# Sheet1.net
KiCad netlist of a schematic drawn in Altium Designer
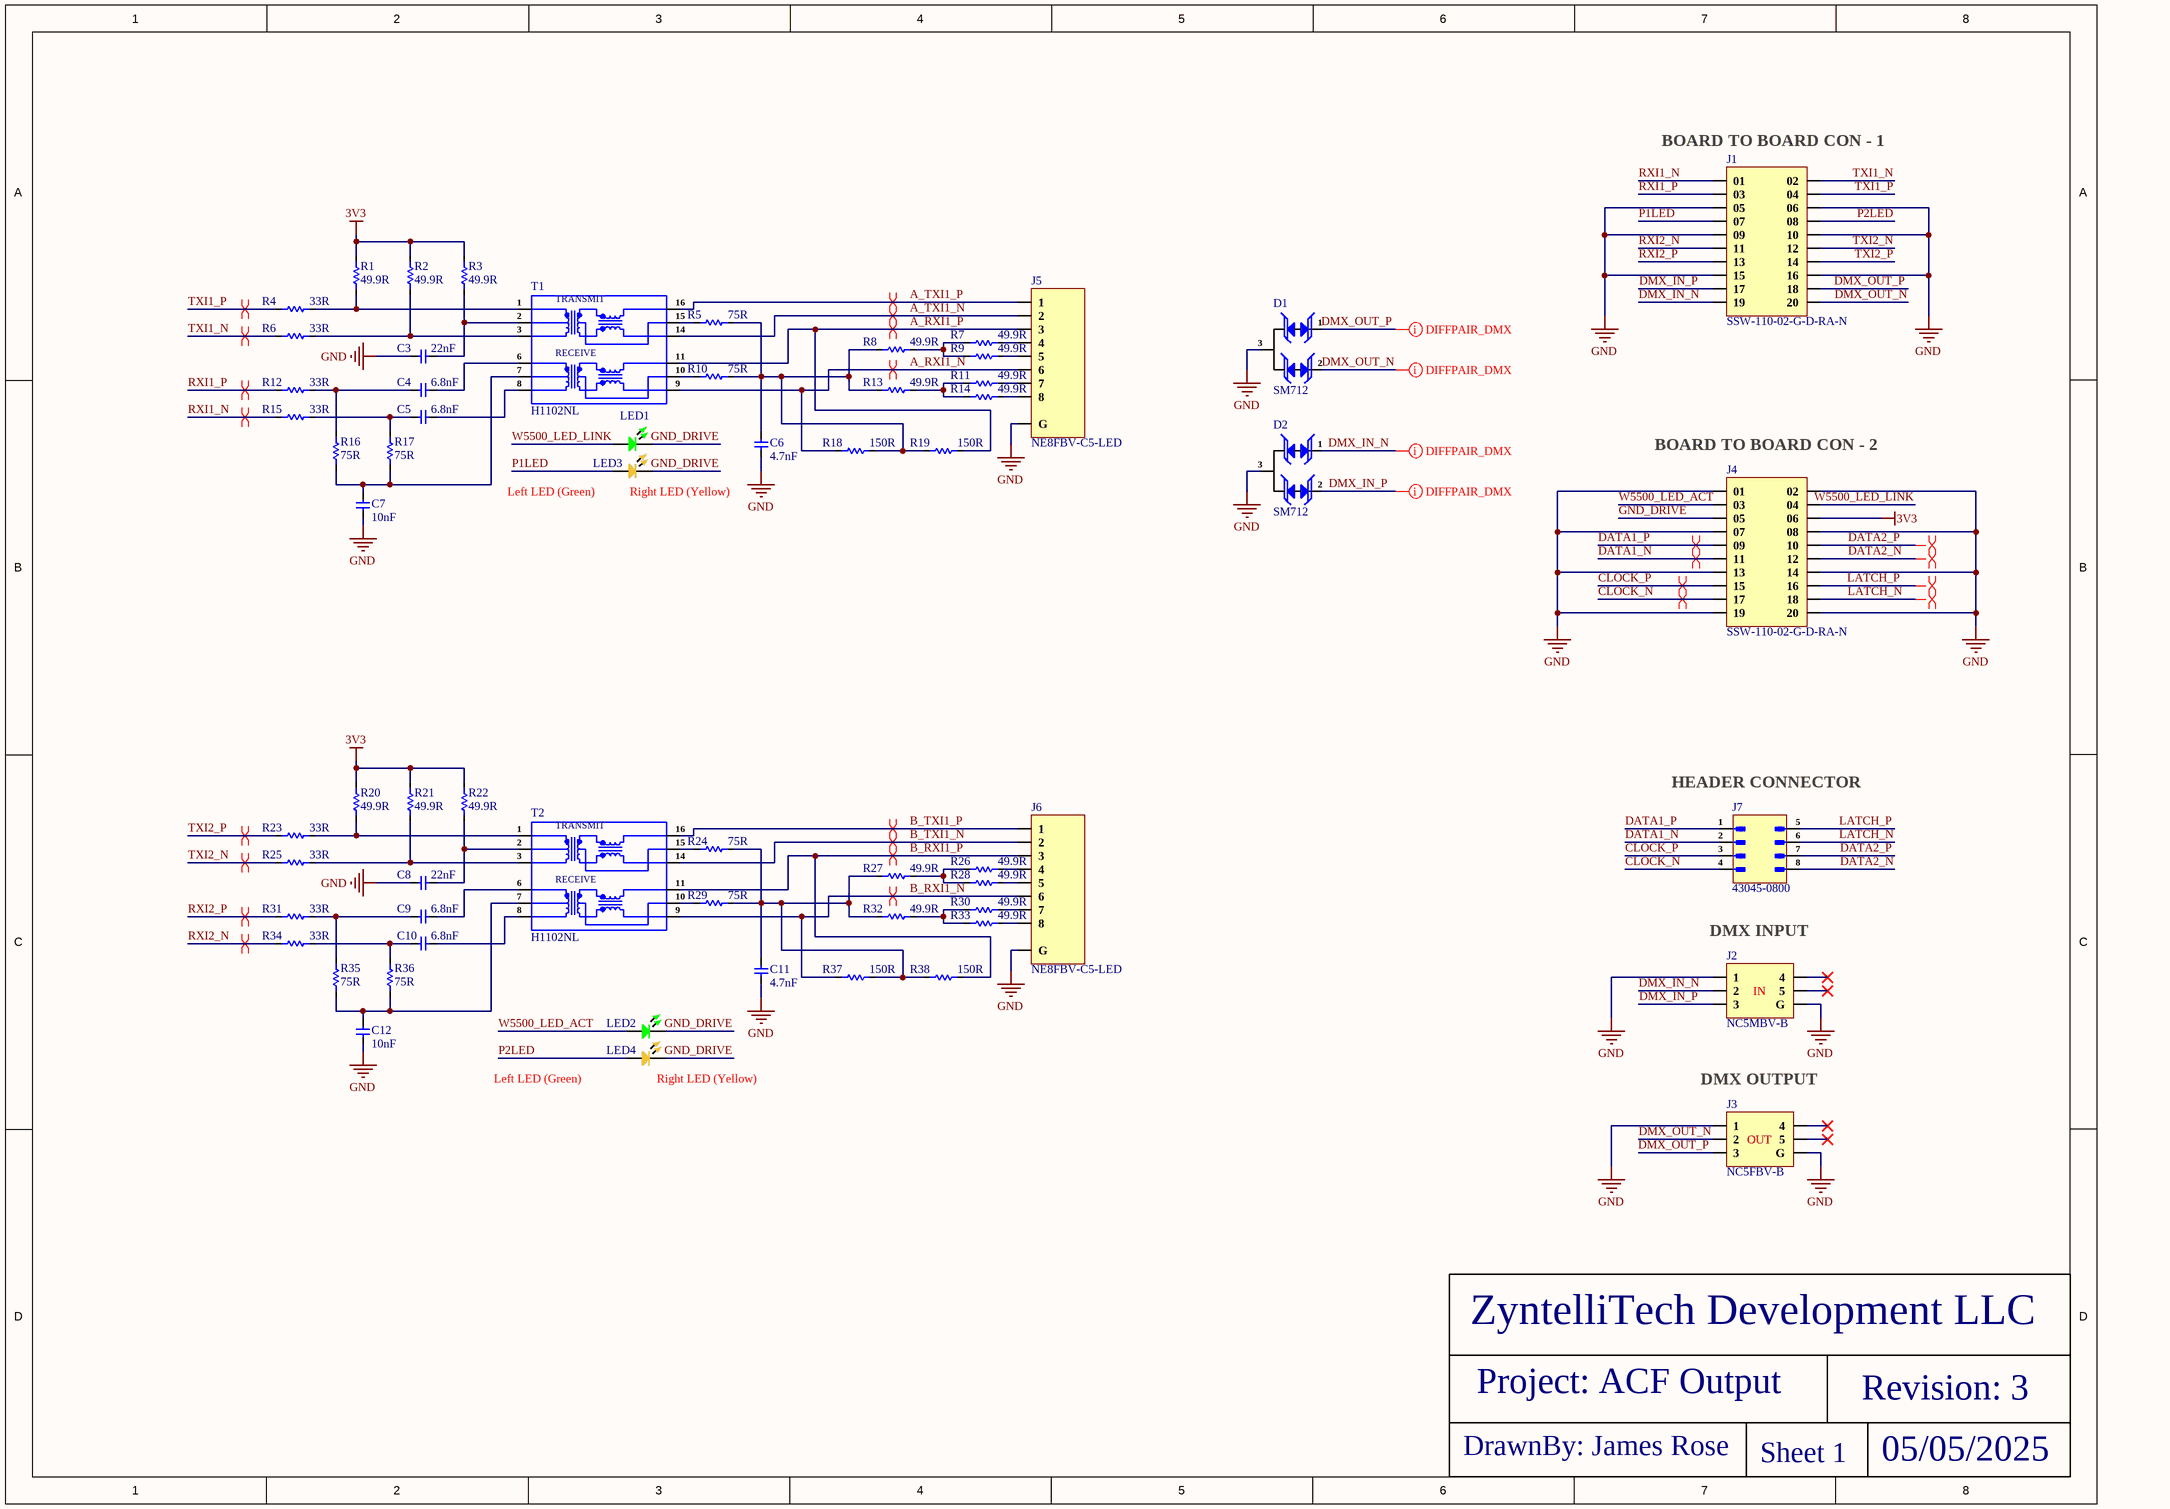
[diagram p0: Sheet1.SchDoc]

(export (version "E")
  (design (tool "Eeschema 10.0.6"))
  (components
    (comp (ref "C3")
      (value "22nF")
      (footprint "Cap-0603")
      (description "CAP CER 0.022UF 50V X7R 0603")
      (fields
        (field (name "MANUFACTURER") "Yageo")
        (field (name "MANUFACTURER PART NUMBER") "CC0603KRX7R9BB223")
      )
      (libsource (lib "eSpark Libraries") (part "CC0603KRX7R9BB223"))
    )
    (comp (ref "C4")
      (value "6.8nF")
      (footprint "Cap-0603")
      (description "50V 6.8nF X7R ±10% 0603")
      (fields (field (name "MANUFACTURER") "FH") (field (name "MANUFACTURER PART NUMBER") "0603B682K500NT"))
      (libsource (lib "eSpark Libraries") (part "0603B682K500NT"))
    )
    (comp (ref "C5")
      (value "6.8nF")
      (footprint "Cap-0603")
      (description "50V 6.8nF X7R ±10% 0603")
      (fields (field (name "MANUFACTURER") "FH") (field (name "MANUFACTURER PART NUMBER") "0603B682K500NT"))
      (libsource (lib "eSpark Libraries") (part "0603B682K500NT"))
    )
    (comp (ref "C6")
      (value "4.7nF")
      (footprint "Cap-1206")
      (description "CAP CER 4700PF 1KV X7R 1206")
      (fields
        (field (name "MANUFACTURER") "Yageo")
        (field (name "MANUFACTURER PART NUMBER") "CC1206KKX7RCBB472")
      )
      (libsource (lib "eSpark Libraries") (part "CC1206KKX7RCBB472"))
    )
    (comp (ref "C7")
      (value "10nF")
      (footprint "Cap-0603")
      (description "CAP CER 10000PF 100V X7R 0603")
      (fields (field (name "LCSC PART NUMBER") "C107059") (field (name "MANUFACTURER") "Yageo"))
      (libsource (lib "eSpark Libraries") (part "CC0603KRX7R0BB103"))
    )
    (comp (ref "C8")
      (value "22nF")
      (footprint "Cap-0603")
      (description "CAP CER 0.022UF 50V X7R 0603")
      (fields
        (field (name "MANUFACTURER") "Yageo")
        (field (name "MANUFACTURER PART NUMBER") "CC0603KRX7R9BB223")
      )
      (libsource (lib "eSpark Libraries") (part "CC0603KRX7R9BB223"))
    )
    (comp (ref "C9")
      (value "6.8nF")
      (footprint "Cap-0603")
      (description "50V 6.8nF X7R ±10% 0603")
      (fields (field (name "MANUFACTURER") "FH") (field (name "MANUFACTURER PART NUMBER") "0603B682K500NT"))
      (libsource (lib "eSpark Libraries") (part "0603B682K500NT"))
    )
    (comp (ref "C10")
      (value "6.8nF")
      (footprint "Cap-0603")
      (description "50V 6.8nF X7R ±10% 0603")
      (fields (field (name "MANUFACTURER") "FH") (field (name "MANUFACTURER PART NUMBER") "0603B682K500NT"))
      (libsource (lib "eSpark Libraries") (part "0603B682K500NT"))
    )
    (comp (ref "C11")
      (value "4.7nF")
      (footprint "Cap-1206")
      (description "CAP CER 4700PF 1KV X7R 1206")
      (fields
        (field (name "MANUFACTURER") "Yageo")
        (field (name "MANUFACTURER PART NUMBER") "CC1206KKX7RCBB472")
      )
      (libsource (lib "eSpark Libraries") (part "CC1206KKX7RCBB472"))
    )
    (comp (ref "C12")
      (value "10nF")
      (footprint "Cap-0603")
      (description "CAP CER 10000PF 100V X7R 0603")
      (fields (field (name "LCSC PART NUMBER") "C107059") (field (name "MANUFACTURER") "Yageo"))
      (libsource (lib "eSpark Libraries") (part "CC0603KRX7R0BB103"))
    )
    (comp (ref "D1")
      (value "SM712")
      (footprint "SOT-23")
      (description "SOT-23 TVS ROHS")
      (fields (field (name "MANUFACTURER") "TECH PUBLIC") (field (name "LCSC PART NUMBER") "C521963"))
      (libsource (lib "eSpark Libraries") (part "SM712"))
    )
    (comp (ref "D2")
      (value "SM712")
      (footprint "SOT-23")
      (description "SOT-23 TVS ROHS")
      (fields (field (name "MANUFACTURER") "TECH PUBLIC") (field (name "LCSC PART NUMBER") "C521963"))
      (libsource (lib "eSpark Libraries") (part "SM712"))
    )
    (comp (ref "J1")
      (value "SSW-110-02-G-D-RA-N")
      (footprint "SSW-110-02-G-D-RA-N")
      (description "CONN RCPT 20POS 0.1 GOLD PCB R/A")
      (fields (field (name "MANUFACTURER") "Samtec"))
      (libsource (lib "eSpark Libraries") (part "SSW-110-02-G-D-RA-N"))
    )
    (comp (ref "J2")
      (value "NC5MBV-B")
      (footprint "NC5MBV-B")
      (description "XLR Connectors 5P M RECEPT B SER PCBV PN 1 GRD SEP BK")
      (fields (field (name "MANUFACTURER") "Neutrik"))
      (libsource (lib "eSpark Libraries") (part "NC5MBV-B"))
    )
    (comp (ref "J3")
      (value "NC5FBV-B")
      (footprint "NC5FBV-B")
      (description "XLR Connectors 5P M RECEPT B SER PCBV PN 1 GRD SEP BK")
      (fields (field (name "MANUFACTURER") "Neutrik"))
      (libsource (lib "eSpark Libraries") (part "NC5FBV-B"))
    )
    (comp (ref "J4")
      (value "SSW-110-02-G-D-RA-N")
      (footprint "SSW-110-02-G-D-RA-N")
      (description "CONN RCPT 20POS 0.1 GOLD PCB R/A")
      (fields (field (name "MANUFACTURER") "Samtec"))
      (libsource (lib "eSpark Libraries") (part "SSW-110-02-G-D-RA-N"))
    )
    (comp (ref "J5")
      (value "NE8FBV-C5-LED")
      (footprint "NE8FBV-C5-LED")
      (description "Modular Connectors / Ethernet Connectors RECP CAT5e B series PCBV, 24mm FP to PCB")
      (fields (field (name "MANUFACTURER") "Neutrik"))
      (libsource (lib "eSpark Libraries") (part "NE8FBV-C5-LED"))
    )
    (comp (ref "J6")
      (value "NE8FBV-C5-LED")
      (footprint "NE8FBV-C5-LED")
      (description "Modular Connectors / Ethernet Connectors RECP CAT5e B series PCBV, 24mm FP to PCB")
      (fields (field (name "MANUFACTURER") "Neutrik"))
      (libsource (lib "eSpark Libraries") (part "NE8FBV-C5-LED"))
    )
    (comp (ref "J7")
      (value "43045-0800")
      (footprint "0430450800")
      (description "CONN HEADER R/A 8POS 3MM")
      (fields (field (name "MANUFACTURER") "Molex"))
      (libsource (lib "eSpark Libraries") (part "43045-0800"))
    )
    (comp (ref "LED1")
      (value "Emerald")
      (footprint "TH LED 3mm_")
      (description "515nm~525nm -30℃~+85℃ Emerald 30° 200mW Plugin,D=3mm Light Emitting Diodes (LED) ROHS")
      (fields
        (field (name "MANUFACTURER") "Foshan NationStar Optoelectronics")
        (field (name "MANUFACTURER PART NUMBER") "NFD3401UGD")
      )
      (libsource (lib "eSpark Libraries") (part "NFD3401UGD"))
    )
    (comp (ref "LED2")
      (value "Emerald")
      (footprint "TH LED 3mm_")
      (description "515nm~525nm -30℃~+85℃ Emerald 30° 200mW Plugin,D=3mm Light Emitting Diodes (LED) ROHS")
      (fields
        (field (name "MANUFACTURER") "Foshan NationStar Optoelectronics")
        (field (name "MANUFACTURER PART NUMBER") "NFD3401UGD")
      )
      (libsource (lib "eSpark Libraries") (part "NFD3401UGD"))
    )
    (comp (ref "LED3")
      (value "Yellow")
      (footprint "TH LED Yellow 3MM")
      (description "585nm~595nm -30℃~+85℃ Yellow 30° 200mW Plugin,D=3mm Light Emitting Diodes (LED) ROHS")
      (fields
        (field (name "MANUFACTURER") "Foshan NationStar Optoelectronics")
        (field (name "MANUFACTURER PART NUMBER") "NFD3401UYD")
      )
      (libsource (lib "eSpark Libraries") (part "NFD3401UYD"))
    )
    (comp (ref "LED4")
      (value "Yellow")
      (footprint "TH LED Yellow 3MM")
      (description "585nm~595nm -30℃~+85℃ Yellow 30° 200mW Plugin,D=3mm Light Emitting Diodes (LED) ROHS")
      (fields
        (field (name "MANUFACTURER") "Foshan NationStar Optoelectronics")
        (field (name "MANUFACTURER PART NUMBER") "NFD3401UYD")
      )
      (libsource (lib "eSpark Libraries") (part "NFD3401UYD"))
    )
    (comp (ref "R1")
      (value "49.9R")
      (footprint "Res-0603")
      (description "RES 49.9 OHM 1% 1/10W 0603")
      (fields
        (field (name "MANUFACTURER") "Yageo")
        (field (name "MANUFACTURER PART NUMBER") "RC0603FR-0749R9L")
      )
      (libsource (lib "eSpark Libraries") (part "RC0603FR-0749R9L"))
    )
    (comp (ref "R2")
      (value "49.9R")
      (footprint "Res-0603")
      (description "RES 49.9 OHM 1% 1/10W 0603")
      (fields
        (field (name "MANUFACTURER") "Yageo")
        (field (name "MANUFACTURER PART NUMBER") "RC0603FR-0749R9L")
      )
      (libsource (lib "eSpark Libraries") (part "RC0603FR-0749R9L"))
    )
    (comp (ref "R3")
      (value "49.9R")
      (footprint "Res-0603")
      (description "RES 49.9 OHM 1% 1/10W 0603")
      (fields
        (field (name "MANUFACTURER") "Yageo")
        (field (name "MANUFACTURER PART NUMBER") "RC0603FR-0749R9L")
      )
      (libsource (lib "eSpark Libraries") (part "RC0603FR-0749R9L"))
    )
    (comp (ref "R4")
      (value "33R")
      (footprint "Res-0603")
      (description "RES SMD 0603 33 Ohm 1% 1/10W")
      (fields
        (field (name "MANUFACTURER") "Yageo")
        (field (name "MANUFACTURER PART NUMBER") "RC0603FR-0733RL")
      )
      (libsource (lib "eSpark Libraries") (part "RC0603FR-0733RL"))
    )
    (comp (ref "R5")
      (value "75R")
      (footprint "Res-0603")
      (description "RES 75 OHM 1% 1/10W 0603")
      (fields
        (field (name "MANUFACTURER") "Yageo")
        (field (name "MANUFACTURER PART NUMBER") "RC0603FR-0775RL")
      )
      (libsource (lib "eSpark Libraries") (part "RC0603FR-0775RL"))
    )
    (comp (ref "R6")
      (value "33R")
      (footprint "Res-0603")
      (description "RES SMD 0603 33 Ohm 1% 1/10W")
      (fields
        (field (name "MANUFACTURER") "Yageo")
        (field (name "MANUFACTURER PART NUMBER") "RC0603FR-0733RL")
      )
      (libsource (lib "eSpark Libraries") (part "RC0603FR-0733RL"))
    )
    (comp (ref "R7")
      (value "49.9R")
      (footprint "Res-0603")
      (description "RES 49.9 OHM 1% 1/10W 0603")
      (fields
        (field (name "MANUFACTURER") "Yageo")
        (field (name "MANUFACTURER PART NUMBER") "RC0603FR-0749R9L")
      )
      (libsource (lib "eSpark Libraries") (part "RC0603FR-0749R9L"))
    )
    (comp (ref "R8")
      (value "49.9R")
      (footprint "Res-0603")
      (description "RES 49.9 OHM 1% 1/10W 0603")
      (fields
        (field (name "MANUFACTURER") "Yageo")
        (field (name "MANUFACTURER PART NUMBER") "RC0603FR-0749R9L")
      )
      (libsource (lib "eSpark Libraries") (part "RC0603FR-0749R9L"))
    )
    (comp (ref "R9")
      (value "49.9R")
      (footprint "Res-0603")
      (description "RES 49.9 OHM 1% 1/10W 0603")
      (fields
        (field (name "MANUFACTURER") "Yageo")
        (field (name "MANUFACTURER PART NUMBER") "RC0603FR-0749R9L")
      )
      (libsource (lib "eSpark Libraries") (part "RC0603FR-0749R9L"))
    )
    (comp (ref "R10")
      (value "75R")
      (footprint "Res-0603")
      (description "RES 75 OHM 1% 1/10W 0603")
      (fields
        (field (name "MANUFACTURER") "Yageo")
        (field (name "MANUFACTURER PART NUMBER") "RC0603FR-0775RL")
      )
      (libsource (lib "eSpark Libraries") (part "RC0603FR-0775RL"))
    )
    (comp (ref "R11")
      (value "49.9R")
      (footprint "Res-0603")
      (description "RES 49.9 OHM 1% 1/10W 0603")
      (fields
        (field (name "MANUFACTURER") "Yageo")
        (field (name "MANUFACTURER PART NUMBER") "RC0603FR-0749R9L")
      )
      (libsource (lib "eSpark Libraries") (part "RC0603FR-0749R9L"))
    )
    (comp (ref "R12")
      (value "33R")
      (footprint "Res-0603")
      (description "RES SMD 0603 33 Ohm 1% 1/10W")
      (fields
        (field (name "MANUFACTURER") "Yageo")
        (field (name "MANUFACTURER PART NUMBER") "RC0603FR-0733RL")
      )
      (libsource (lib "eSpark Libraries") (part "RC0603FR-0733RL"))
    )
    (comp (ref "R13")
      (value "49.9R")
      (footprint "Res-0603")
      (description "RES 49.9 OHM 1% 1/10W 0603")
      (fields
        (field (name "MANUFACTURER") "Yageo")
        (field (name "MANUFACTURER PART NUMBER") "RC0603FR-0749R9L")
      )
      (libsource (lib "eSpark Libraries") (part "RC0603FR-0749R9L"))
    )
    (comp (ref "R14")
      (value "49.9R")
      (footprint "Res-0603")
      (description "RES 49.9 OHM 1% 1/10W 0603")
      (fields
        (field (name "MANUFACTURER") "Yageo")
        (field (name "MANUFACTURER PART NUMBER") "RC0603FR-0749R9L")
      )
      (libsource (lib "eSpark Libraries") (part "RC0603FR-0749R9L"))
    )
    (comp (ref "R15")
      (value "33R")
      (footprint "Res-0603")
      (description "RES SMD 0603 33 Ohm 1% 1/10W")
      (fields
        (field (name "MANUFACTURER") "Yageo")
        (field (name "MANUFACTURER PART NUMBER") "RC0603FR-0733RL")
      )
      (libsource (lib "eSpark Libraries") (part "RC0603FR-0733RL"))
    )
    (comp (ref "R16")
      (value "75R")
      (footprint "Res-0603")
      (description "RES 75 OHM 1% 1/10W 0603")
      (fields
        (field (name "MANUFACTURER") "Yageo")
        (field (name "MANUFACTURER PART NUMBER") "RC0603FR-0775RL")
      )
      (libsource (lib "eSpark Libraries") (part "RC0603FR-0775RL"))
    )
    (comp (ref "R17")
      (value "75R")
      (footprint "Res-0603")
      (description "RES 75 OHM 1% 1/10W 0603")
      (fields
        (field (name "MANUFACTURER") "Yageo")
        (field (name "MANUFACTURER PART NUMBER") "RC0603FR-0775RL")
      )
      (libsource (lib "eSpark Libraries") (part "RC0603FR-0775RL"))
    )
    (comp (ref "R18")
      (value "150R")
      (footprint "Res-0603")
      (description "RES SMD 150OHM 1/10W 0603")
      (fields
        (field (name "MANUFACTURER") "Yageo")
        (field (name "MANUFACTURER PART NUMBER") "RC0603FR-07150RL")
      )
      (libsource (lib "eSpark Libraries") (part "RC0603FR-07150RL"))
    )
    (comp (ref "R19")
      (value "150R")
      (footprint "Res-0603")
      (description "RES SMD 150OHM 1/10W 0603")
      (fields
        (field (name "MANUFACTURER") "Yageo")
        (field (name "MANUFACTURER PART NUMBER") "RC0603FR-07150RL")
      )
      (libsource (lib "eSpark Libraries") (part "RC0603FR-07150RL"))
    )
    (comp (ref "R20")
      (value "49.9R")
      (footprint "Res-0603")
      (description "RES 49.9 OHM 1% 1/10W 0603")
      (fields
        (field (name "MANUFACTURER") "Yageo")
        (field (name "MANUFACTURER PART NUMBER") "RC0603FR-0749R9L")
      )
      (libsource (lib "eSpark Libraries") (part "RC0603FR-0749R9L"))
    )
    (comp (ref "R21")
      (value "49.9R")
      (footprint "Res-0603")
      (description "RES 49.9 OHM 1% 1/10W 0603")
      (fields
        (field (name "MANUFACTURER") "Yageo")
        (field (name "MANUFACTURER PART NUMBER") "RC0603FR-0749R9L")
      )
      (libsource (lib "eSpark Libraries") (part "RC0603FR-0749R9L"))
    )
    (comp (ref "R22")
      (value "49.9R")
      (footprint "Res-0603")
      (description "RES 49.9 OHM 1% 1/10W 0603")
      (fields
        (field (name "MANUFACTURER") "Yageo")
        (field (name "MANUFACTURER PART NUMBER") "RC0603FR-0749R9L")
      )
      (libsource (lib "eSpark Libraries") (part "RC0603FR-0749R9L"))
    )
    (comp (ref "R23")
      (value "33R")
      (footprint "Res-0603")
      (description "RES SMD 0603 33 Ohm 1% 1/10W")
      (fields
        (field (name "MANUFACTURER") "Yageo")
        (field (name "MANUFACTURER PART NUMBER") "RC0603FR-0733RL")
      )
      (libsource (lib "eSpark Libraries") (part "RC0603FR-0733RL"))
    )
    (comp (ref "R24")
      (value "75R")
      (footprint "Res-0603")
      (description "RES 75 OHM 1% 1/10W 0603")
      (fields
        (field (name "MANUFACTURER") "Yageo")
        (field (name "MANUFACTURER PART NUMBER") "RC0603FR-0775RL")
      )
      (libsource (lib "eSpark Libraries") (part "RC0603FR-0775RL"))
    )
    (comp (ref "R25")
      (value "33R")
      (footprint "Res-0603")
      (description "RES SMD 0603 33 Ohm 1% 1/10W")
      (fields
        (field (name "MANUFACTURER") "Yageo")
        (field (name "MANUFACTURER PART NUMBER") "RC0603FR-0733RL")
      )
      (libsource (lib "eSpark Libraries") (part "RC0603FR-0733RL"))
    )
    (comp (ref "R26")
      (value "49.9R")
      (footprint "Res-0603")
      (description "RES 49.9 OHM 1% 1/10W 0603")
      (fields
        (field (name "MANUFACTURER") "Yageo")
        (field (name "MANUFACTURER PART NUMBER") "RC0603FR-0749R9L")
      )
      (libsource (lib "eSpark Libraries") (part "RC0603FR-0749R9L"))
    )
    (comp (ref "R27")
      (value "49.9R")
      (footprint "Res-0603")
      (description "RES 49.9 OHM 1% 1/10W 0603")
      (fields
        (field (name "MANUFACTURER") "Yageo")
        (field (name "MANUFACTURER PART NUMBER") "RC0603FR-0749R9L")
      )
      (libsource (lib "eSpark Libraries") (part "RC0603FR-0749R9L"))
    )
    (comp (ref "R28")
      (value "49.9R")
      (footprint "Res-0603")
      (description "RES 49.9 OHM 1% 1/10W 0603")
      (fields
        (field (name "MANUFACTURER") "Yageo")
        (field (name "MANUFACTURER PART NUMBER") "RC0603FR-0749R9L")
      )
      (libsource (lib "eSpark Libraries") (part "RC0603FR-0749R9L"))
    )
    (comp (ref "R29")
      (value "75R")
      (footprint "Res-0603")
      (description "RES 75 OHM 1% 1/10W 0603")
      (fields
        (field (name "MANUFACTURER") "Yageo")
        (field (name "MANUFACTURER PART NUMBER") "RC0603FR-0775RL")
      )
      (libsource (lib "eSpark Libraries") (part "RC0603FR-0775RL"))
    )
    (comp (ref "R30")
      (value "49.9R")
      (footprint "Res-0603")
      (description "RES 49.9 OHM 1% 1/10W 0603")
      (fields
        (field (name "MANUFACTURER") "Yageo")
        (field (name "MANUFACTURER PART NUMBER") "RC0603FR-0749R9L")
      )
      (libsource (lib "eSpark Libraries") (part "RC0603FR-0749R9L"))
    )
    (comp (ref "R31")
      (value "33R")
      (footprint "Res-0603")
      (description "RES SMD 0603 33 Ohm 1% 1/10W")
      (fields
        (field (name "MANUFACTURER") "Yageo")
        (field (name "MANUFACTURER PART NUMBER") "RC0603FR-0733RL")
      )
      (libsource (lib "eSpark Libraries") (part "RC0603FR-0733RL"))
    )
    (comp (ref "R32")
      (value "49.9R")
      (footprint "Res-0603")
      (description "RES 49.9 OHM 1% 1/10W 0603")
      (fields
        (field (name "MANUFACTURER") "Yageo")
        (field (name "MANUFACTURER PART NUMBER") "RC0603FR-0749R9L")
      )
      (libsource (lib "eSpark Libraries") (part "RC0603FR-0749R9L"))
    )
    (comp (ref "R33")
      (value "49.9R")
      (footprint "Res-0603")
      (description "RES 49.9 OHM 1% 1/10W 0603")
      (fields
        (field (name "MANUFACTURER") "Yageo")
        (field (name "MANUFACTURER PART NUMBER") "RC0603FR-0749R9L")
      )
      (libsource (lib "eSpark Libraries") (part "RC0603FR-0749R9L"))
    )
    (comp (ref "R34")
      (value "33R")
      (footprint "Res-0603")
      (description "RES SMD 0603 33 Ohm 1% 1/10W")
      (fields
        (field (name "MANUFACTURER") "Yageo")
        (field (name "MANUFACTURER PART NUMBER") "RC0603FR-0733RL")
      )
      (libsource (lib "eSpark Libraries") (part "RC0603FR-0733RL"))
    )
    (comp (ref "R35")
      (value "75R")
      (footprint "Res-0603")
      (description "RES 75 OHM 1% 1/10W 0603")
      (fields
        (field (name "MANUFACTURER") "Yageo")
        (field (name "MANUFACTURER PART NUMBER") "RC0603FR-0775RL")
      )
      (libsource (lib "eSpark Libraries") (part "RC0603FR-0775RL"))
    )
    (comp (ref "R36")
      (value "75R")
      (footprint "Res-0603")
      (description "RES 75 OHM 1% 1/10W 0603")
      (fields
        (field (name "MANUFACTURER") "Yageo")
        (field (name "MANUFACTURER PART NUMBER") "RC0603FR-0775RL")
      )
      (libsource (lib "eSpark Libraries") (part "RC0603FR-0775RL"))
    )
    (comp (ref "R37")
      (value "150R")
      (footprint "Res-0603")
      (description "RES SMD 150OHM 1/10W 0603")
      (fields
        (field (name "MANUFACTURER") "Yageo")
        (field (name "MANUFACTURER PART NUMBER") "RC0603FR-07150RL")
      )
      (libsource (lib "eSpark Libraries") (part "RC0603FR-07150RL"))
    )
    (comp (ref "R38")
      (value "150R")
      (footprint "Res-0603")
      (description "RES SMD 150OHM 1/10W 0603")
      (fields
        (field (name "MANUFACTURER") "Yageo")
        (field (name "MANUFACTURER PART NUMBER") "RC0603FR-07150RL")
      )
      (libsource (lib "eSpark Libraries") (part "RC0603FR-07150RL"))
    )
    (comp (ref "T1")
      (value "H1102NL")
      (footprint "H1102NLT")
      (description "XFRMR MAGNETIC 1PORT 1:1 10/100")
      (fields (field (name "MANUFACTURER") "Pulse") (field (name "LCSC PART NUMBER") "C18584"))
      (libsource (lib "eSpark Libraries") (part "H1102NL"))
    )
    (comp (ref "T2")
      (value "H1102NL")
      (footprint "H1102NLT")
      (description "XFRMR MAGNETIC 1PORT 1:1 10/100")
      (fields (field (name "MANUFACTURER") "Pulse") (field (name "LCSC PART NUMBER") "C18584"))
      (libsource (lib "eSpark Libraries") (part "H1102NL"))
    )
  )
  (nets
    (net (code "1") (name "/A_RXI1_N") (class "Default")
      (node (ref "J5") (pin "6") (pinfunction "6_6") (pintype "passive"))
      (node (ref "R18") (pin "2") (pinfunction "2_2") (pintype "passive"))
      (node (ref "T1") (pin "9") (pinfunction "9_9") (pintype "passive"))
    )
    (net (code "2") (name "/A_RXI1_P") (class "Default")
      (node (ref "J5") (pin "3") (pinfunction "3_3") (pintype "passive"))
      (node (ref "R19") (pin "1") (pinfunction "1_1") (pintype "passive"))
      (node (ref "T1") (pin "11") (pinfunction "11_11") (pintype "passive"))
    )
    (net (code "3") (name "/A_TXI1_N") (class "Default")
      (node (ref "J5") (pin "2") (pinfunction "2_2") (pintype "passive"))
      (node (ref "T1") (pin "14") (pinfunction "14_14") (pintype "passive"))
    )
    (net (code "4") (name "/A_TXI1_P") (class "Default")
      (node (ref "J5") (pin "1") (pinfunction "1_1") (pintype "passive"))
      (node (ref "T1") (pin "16") (pinfunction "16_16") (pintype "passive"))
    )
    (net (code "5") (name "/B_RXI1_N") (class "Default")
      (node (ref "J6") (pin "6") (pinfunction "6_6") (pintype "passive"))
      (node (ref "R37") (pin "2") (pinfunction "2_2") (pintype "passive"))
      (node (ref "T2") (pin "9") (pinfunction "9_9") (pintype "passive"))
    )
    (net (code "6") (name "/B_RXI1_P") (class "Default")
      (node (ref "J6") (pin "3") (pinfunction "3_3") (pintype "passive"))
      (node (ref "R38") (pin "1") (pinfunction "1_1") (pintype "passive"))
      (node (ref "T2") (pin "11") (pinfunction "11_11") (pintype "passive"))
    )
    (net (code "7") (name "/B_TXI1_N") (class "Default")
      (node (ref "J6") (pin "2") (pinfunction "2_2") (pintype "passive"))
      (node (ref "T2") (pin "14") (pinfunction "14_14") (pintype "passive"))
    )
    (net (code "8") (name "/B_TXI1_P") (class "Default")
      (node (ref "J6") (pin "1") (pinfunction "1_1") (pintype "passive"))
      (node (ref "T2") (pin "16") (pinfunction "16_16") (pintype "passive"))
    )
    (net (code "9") (name "/CLOCK_N") (class "Default")
      (node (ref "J4") (pin "17") (pinfunction "17_17") (pintype "passive"))
      (node (ref "J7") (pin "4") (pinfunction "4_4") (pintype "passive"))
    )
    (net (code "10") (name "/CLOCK_P") (class "Default")
      (node (ref "J4") (pin "15") (pinfunction "15_15") (pintype "passive"))
      (node (ref "J7") (pin "3") (pinfunction "3_3") (pintype "passive"))
    )
    (net (code "11") (name "/DATA1_N") (class "Default")
      (node (ref "J4") (pin "11") (pinfunction "11_11") (pintype "passive"))
      (node (ref "J7") (pin "2") (pinfunction "2_2") (pintype "passive"))
    )
    (net (code "12") (name "/DATA1_P") (class "Default")
      (node (ref "J4") (pin "09") (pinfunction "09_09") (pintype "passive"))
      (node (ref "J7") (pin "1") (pinfunction "1_1") (pintype "passive"))
    )
    (net (code "13") (name "/DATA2_N") (class "Default")
      (node (ref "J4") (pin "12") (pinfunction "12_12") (pintype "passive"))
      (node (ref "J7") (pin "8") (pinfunction "8_8") (pintype "passive"))
    )
    (net (code "14") (name "/DATA2_P") (class "Default")
      (node (ref "J4") (pin "10") (pinfunction "10_10") (pintype "passive"))
      (node (ref "J7") (pin "7") (pinfunction "7_7") (pintype "passive"))
    )
    (net (code "15") (name "/DMX_IN_N") (class "Default")
      (node (ref "D2") (pin "1") (pinfunction "I/O1_1") (pintype "passive"))
      (node (ref "J1") (pin "19") (pinfunction "19_19") (pintype "passive"))
      (node (ref "J2") (pin "2") (pinfunction "2_2") (pintype "passive"))
    )
    (net (code "16") (name "/DMX_IN_P") (class "Default")
      (node (ref "D2") (pin "2") (pinfunction "I/O2_2") (pintype "passive"))
      (node (ref "J1") (pin "17") (pinfunction "17_17") (pintype "passive"))
      (node (ref "J2") (pin "3") (pinfunction "3_3") (pintype "passive"))
    )
    (net (code "17") (name "/DMX_OUT_N") (class "Default")
      (node (ref "D1") (pin "2") (pinfunction "I/O2_2") (pintype "passive"))
      (node (ref "J1") (pin "20") (pinfunction "20_20") (pintype "passive"))
      (node (ref "J3") (pin "2") (pinfunction "2_2") (pintype "passive"))
    )
    (net (code "18") (name "/DMX_OUT_P") (class "Default")
      (node (ref "D1") (pin "1") (pinfunction "I/O1_1") (pintype "passive"))
      (node (ref "J1") (pin "18") (pinfunction "18_18") (pintype "passive"))
      (node (ref "J3") (pin "3") (pinfunction "3_3") (pintype "passive"))
    )
    (net (code "19") (name "/GND_DRIVE") (class "Default")
      (node (ref "J4") (pin "05") (pinfunction "05_05") (pintype "passive"))
      (node (ref "LED1") (pin "1") (pinfunction "-_1") (pintype "passive"))
      (node (ref "LED2") (pin "1") (pinfunction "-_1") (pintype "passive"))
      (node (ref "LED3") (pin "2") (pinfunction "2_2") (pintype "passive"))
      (node (ref "LED4") (pin "2") (pinfunction "2_2") (pintype "passive"))
    )
    (net (code "20") (name "/LATCH_N") (class "Default")
      (node (ref "J4") (pin "18") (pinfunction "18_18") (pintype "passive"))
      (node (ref "J7") (pin "6") (pinfunction "6_6") (pintype "passive"))
    )
    (net (code "21") (name "/LATCH_P") (class "Default")
      (node (ref "J4") (pin "16") (pinfunction "16_16") (pintype "passive"))
      (node (ref "J7") (pin "5") (pinfunction "5_5") (pintype "passive"))
    )
    (net (code "22") (name "/P1LED") (class "Default")
      (node (ref "J1") (pin "07") (pinfunction "07_07") (pintype "passive"))
      (node (ref "LED3") (pin "1") (pinfunction "1_1") (pintype "passive"))
    )
    (net (code "23") (name "/P2LED") (class "Default")
      (node (ref "J1") (pin "08") (pinfunction "08_08") (pintype "passive"))
      (node (ref "LED4") (pin "1") (pinfunction "1_1") (pintype "passive"))
    )
    (net (code "24") (name "/RXI1_N") (class "Default")
      (node (ref "J1") (pin "01") (pinfunction "01_01") (pintype "passive"))
      (node (ref "R15") (pin "1") (pinfunction "1_1") (pintype "passive"))
    )
    (net (code "25") (name "/RXI1_P") (class "Default")
      (node (ref "J1") (pin "03") (pinfunction "03_03") (pintype "passive"))
      (node (ref "R12") (pin "1") (pinfunction "1_1") (pintype "passive"))
    )
    (net (code "26") (name "/RXI2_N") (class "Default")
      (node (ref "J1") (pin "11") (pinfunction "11_11") (pintype "passive"))
      (node (ref "R34") (pin "1") (pinfunction "1_1") (pintype "passive"))
    )
    (net (code "27") (name "/RXI2_P") (class "Default")
      (node (ref "J1") (pin "13") (pinfunction "13_13") (pintype "passive"))
      (node (ref "R31") (pin "1") (pinfunction "1_1") (pintype "passive"))
    )
    (net (code "28") (name "/TXI1_N") (class "Default")
      (node (ref "J1") (pin "02") (pinfunction "02_02") (pintype "passive"))
      (node (ref "R6") (pin "1") (pinfunction "1_1") (pintype "passive"))
    )
    (net (code "29") (name "/TXI1_P") (class "Default")
      (node (ref "J1") (pin "04") (pinfunction "04_04") (pintype "passive"))
      (node (ref "R4") (pin "1") (pinfunction "1_1") (pintype "passive"))
    )
    (net (code "30") (name "/TXI2_N") (class "Default")
      (node (ref "J1") (pin "12") (pinfunction "12_12") (pintype "passive"))
      (node (ref "R25") (pin "1") (pinfunction "1_1") (pintype "passive"))
    )
    (net (code "31") (name "/TXI2_P") (class "Default")
      (node (ref "J1") (pin "14") (pinfunction "14_14") (pintype "passive"))
      (node (ref "R23") (pin "1") (pinfunction "1_1") (pintype "passive"))
    )
    (net (code "32") (name "/W5500_LED_ACT") (class "Default")
      (node (ref "J4") (pin "03") (pinfunction "03_03") (pintype "passive"))
      (node (ref "LED2") (pin "2") (pinfunction "+_2") (pintype "passive"))
    )
    (net (code "33") (name "/W5500_LED_LINK") (class "Default")
      (node (ref "J4") (pin "04") (pinfunction "04_04") (pintype "passive"))
      (node (ref "LED1") (pin "2") (pinfunction "+_2") (pintype "passive"))
    )
    (net (code "34") (name "3V3") (class "Default")
      (node (ref "J4") (pin "06") (pinfunction "06_06") (pintype "passive"))
      (node (ref "R1") (pin "1") (pinfunction "1_1") (pintype "passive"))
      (node (ref "R2") (pin "1") (pinfunction "1_1") (pintype "passive"))
      (node (ref "R20") (pin "1") (pinfunction "1_1") (pintype "passive"))
      (node (ref "R21") (pin "1") (pinfunction "1_1") (pintype "passive"))
      (node (ref "R22") (pin "1") (pinfunction "1_1") (pintype "passive"))
      (node (ref "R3") (pin "1") (pinfunction "1_1") (pintype "passive"))
    )
    (net (code "35") (name "GND") (class "Default")
      (node (ref "C11") (pin "1") (pinfunction "1_1") (pintype "passive"))
      (node (ref "C12") (pin "1") (pinfunction "1_1") (pintype "passive"))
      (node (ref "C3") (pin "1") (pinfunction "1_1") (pintype "passive"))
      (node (ref "C6") (pin "1") (pinfunction "1_1") (pintype "passive"))
      (node (ref "C7") (pin "1") (pinfunction "1_1") (pintype "passive"))
      (node (ref "C8") (pin "1") (pinfunction "1_1") (pintype "passive"))
      (node (ref "D1") (pin "3") (pinfunction "GND_3") (pintype "passive"))
      (node (ref "D2") (pin "3") (pinfunction "GND_3") (pintype "passive"))
      (node (ref "J1") (pin "05") (pinfunction "05_05") (pintype "passive"))
      (node (ref "J1") (pin "06") (pinfunction "06_06") (pintype "passive"))
      (node (ref "J1") (pin "09") (pinfunction "09_09") (pintype "passive"))
      (node (ref "J1") (pin "10") (pinfunction "10_10") (pintype "passive"))
      (node (ref "J1") (pin "15") (pinfunction "15_15") (pintype "passive"))
      (node (ref "J1") (pin "16") (pinfunction "16_16") (pintype "passive"))
      (node (ref "J2") (pin "1") (pinfunction "1_1") (pintype "passive"))
      (node (ref "J2") (pin "G") (pinfunction "G_G") (pintype "passive"))
      (node (ref "J3") (pin "1") (pinfunction "1_1") (pintype "passive"))
      (node (ref "J3") (pin "G") (pinfunction "G_G") (pintype "passive"))
      (node (ref "J4") (pin "01") (pinfunction "01_01") (pintype "passive"))
      (node (ref "J4") (pin "02") (pinfunction "02_02") (pintype "passive"))
      (node (ref "J4") (pin "07") (pinfunction "07_07") (pintype "passive"))
      (node (ref "J4") (pin "08") (pinfunction "08_08") (pintype "passive"))
      (node (ref "J4") (pin "13") (pinfunction "13_13") (pintype "passive"))
      (node (ref "J4") (pin "14") (pinfunction "14_14") (pintype "passive"))
      (node (ref "J4") (pin "19") (pinfunction "19_19") (pintype "passive"))
      (node (ref "J4") (pin "20") (pinfunction "20_20") (pintype "passive"))
      (node (ref "J5") (pin "G") (pinfunction "G_G") (pintype "power_in"))
      (node (ref "J6") (pin "G") (pinfunction "G_G") (pintype "power_in"))
    )
    (net (code "36") (name "Net-(C3-Pad2)") (class "Default")
      (node (ref "C3") (pin "2") (pinfunction "2_2") (pintype "passive"))
      (node (ref "R3") (pin "2") (pinfunction "2_2") (pintype "passive"))
      (node (ref "T1") (pin "2") (pinfunction "2_2") (pintype "passive"))
    )
    (net (code "37") (name "Net-(C4-Pad1)") (class "Default")
      (node (ref "C4") (pin "1") (pinfunction "1_1") (pintype "passive"))
      (node (ref "R12") (pin "2") (pinfunction "2_2") (pintype "passive"))
      (node (ref "R16") (pin "1") (pinfunction "1_1") (pintype "passive"))
    )
    (net (code "38") (name "Net-(C4-Pad2)") (class "Default")
      (node (ref "C4") (pin "2") (pinfunction "2_2") (pintype "passive"))
      (node (ref "T1") (pin "6") (pinfunction "6_6") (pintype "passive"))
    )
    (net (code "39") (name "Net-(C5-Pad1)") (class "Default")
      (node (ref "C5") (pin "1") (pinfunction "1_1") (pintype "passive"))
      (node (ref "R15") (pin "2") (pinfunction "2_2") (pintype "passive"))
      (node (ref "R17") (pin "1") (pinfunction "1_1") (pintype "passive"))
    )
    (net (code "40") (name "Net-(C5-Pad2)") (class "Default")
      (node (ref "C5") (pin "2") (pinfunction "2_2") (pintype "passive"))
      (node (ref "T1") (pin "8") (pinfunction "8_8") (pintype "passive"))
    )
    (net (code "41") (name "Net-(C6-Pad2)") (class "Default")
      (node (ref "C6") (pin "2") (pinfunction "2_2") (pintype "passive"))
      (node (ref "R10") (pin "1") (pinfunction "1_1") (pintype "passive"))
      (node (ref "R13") (pin "2") (pinfunction "2_2") (pintype "passive"))
      (node (ref "R18") (pin "1") (pinfunction "1_1") (pintype "passive"))
      (node (ref "R19") (pin "2") (pinfunction "2_2") (pintype "passive"))
      (node (ref "R5") (pin "1") (pinfunction "1_1") (pintype "passive"))
      (node (ref "R8") (pin "2") (pinfunction "2_2") (pintype "passive"))
    )
    (net (code "42") (name "Net-(C7-Pad2)") (class "Default")
      (node (ref "C7") (pin "2") (pinfunction "2_2") (pintype "passive"))
      (node (ref "R16") (pin "2") (pinfunction "2_2") (pintype "passive"))
      (node (ref "R17") (pin "2") (pinfunction "2_2") (pintype "passive"))
      (node (ref "T1") (pin "7") (pinfunction "7_7") (pintype "passive"))
    )
    (net (code "43") (name "Net-(C8-Pad2)") (class "Default")
      (node (ref "C8") (pin "2") (pinfunction "2_2") (pintype "passive"))
      (node (ref "R22") (pin "2") (pinfunction "2_2") (pintype "passive"))
      (node (ref "T2") (pin "2") (pinfunction "2_2") (pintype "passive"))
    )
    (net (code "44") (name "Net-(C9-Pad1)") (class "Default")
      (node (ref "C9") (pin "1") (pinfunction "1_1") (pintype "passive"))
      (node (ref "R31") (pin "2") (pinfunction "2_2") (pintype "passive"))
      (node (ref "R35") (pin "1") (pinfunction "1_1") (pintype "passive"))
    )
    (net (code "45") (name "Net-(C9-Pad2)") (class "Default")
      (node (ref "C9") (pin "2") (pinfunction "2_2") (pintype "passive"))
      (node (ref "T2") (pin "6") (pinfunction "6_6") (pintype "passive"))
    )
    (net (code "46") (name "Net-(C10-Pad1)") (class "Default")
      (node (ref "C10") (pin "1") (pinfunction "1_1") (pintype "passive"))
      (node (ref "R34") (pin "2") (pinfunction "2_2") (pintype "passive"))
      (node (ref "R36") (pin "1") (pinfunction "1_1") (pintype "passive"))
    )
    (net (code "47") (name "Net-(C10-Pad2)") (class "Default")
      (node (ref "C10") (pin "2") (pinfunction "2_2") (pintype "passive"))
      (node (ref "T2") (pin "8") (pinfunction "8_8") (pintype "passive"))
    )
    (net (code "48") (name "Net-(C11-Pad2)") (class "Default")
      (node (ref "C11") (pin "2") (pinfunction "2_2") (pintype "passive"))
      (node (ref "R24") (pin "1") (pinfunction "1_1") (pintype "passive"))
      (node (ref "R27") (pin "2") (pinfunction "2_2") (pintype "passive"))
      (node (ref "R29") (pin "1") (pinfunction "1_1") (pintype "passive"))
      (node (ref "R32") (pin "2") (pinfunction "2_2") (pintype "passive"))
      (node (ref "R37") (pin "1") (pinfunction "1_1") (pintype "passive"))
      (node (ref "R38") (pin "2") (pinfunction "2_2") (pintype "passive"))
    )
    (net (code "49") (name "Net-(C12-Pad2)") (class "Default")
      (node (ref "C12") (pin "2") (pinfunction "2_2") (pintype "passive"))
      (node (ref "R35") (pin "2") (pinfunction "2_2") (pintype "passive"))
      (node (ref "R36") (pin "2") (pinfunction "2_2") (pintype "passive"))
      (node (ref "T2") (pin "7") (pinfunction "7_7") (pintype "passive"))
    )
    (net (code "50") (name "Net-(J5-Pad4)") (class "Default")
      (node (ref "J5") (pin "4") (pinfunction "4_4") (pintype "passive"))
      (node (ref "R7") (pin "1") (pinfunction "1_1") (pintype "passive"))
    )
    (net (code "51") (name "Net-(J5-Pad5)") (class "Default")
      (node (ref "J5") (pin "5") (pinfunction "5_5") (pintype "passive"))
      (node (ref "R9") (pin "1") (pinfunction "1_1") (pintype "passive"))
    )
    (net (code "52") (name "Net-(J5-Pad7)") (class "Default")
      (node (ref "J5") (pin "7") (pinfunction "7_7") (pintype "passive"))
      (node (ref "R11") (pin "1") (pinfunction "1_1") (pintype "passive"))
    )
    (net (code "53") (name "Net-(J5-Pad8)") (class "Default")
      (node (ref "J5") (pin "8") (pinfunction "8_8") (pintype "passive"))
      (node (ref "R14") (pin "1") (pinfunction "1_1") (pintype "passive"))
    )
    (net (code "54") (name "Net-(J6-Pad4)") (class "Default")
      (node (ref "J6") (pin "4") (pinfunction "4_4") (pintype "passive"))
      (node (ref "R26") (pin "1") (pinfunction "1_1") (pintype "passive"))
    )
    (net (code "55") (name "Net-(J6-Pad5)") (class "Default")
      (node (ref "J6") (pin "5") (pinfunction "5_5") (pintype "passive"))
      (node (ref "R28") (pin "1") (pinfunction "1_1") (pintype "passive"))
    )
    (net (code "56") (name "Net-(J6-Pad7)") (class "Default")
      (node (ref "J6") (pin "7") (pinfunction "7_7") (pintype "passive"))
      (node (ref "R30") (pin "1") (pinfunction "1_1") (pintype "passive"))
    )
    (net (code "57") (name "Net-(J6-Pad8)") (class "Default")
      (node (ref "J6") (pin "8") (pinfunction "8_8") (pintype "passive"))
      (node (ref "R33") (pin "1") (pinfunction "1_1") (pintype "passive"))
    )
    (net (code "58") (name "Net-(R1-Pad2)") (class "Default")
      (node (ref "R1") (pin "2") (pinfunction "2_2") (pintype "passive"))
      (node (ref "R4") (pin "2") (pinfunction "2_2") (pintype "passive"))
      (node (ref "T1") (pin "1") (pinfunction "1_1") (pintype "passive"))
    )
    (net (code "59") (name "Net-(R2-Pad2)") (class "Default")
      (node (ref "R2") (pin "2") (pinfunction "2_2") (pintype "passive"))
      (node (ref "R6") (pin "2") (pinfunction "2_2") (pintype "passive"))
      (node (ref "T1") (pin "3") (pinfunction "3_3") (pintype "passive"))
    )
    (net (code "60") (name "Net-(R5-Pad2)") (class "Default")
      (node (ref "R5") (pin "2") (pinfunction "2_2") (pintype "passive"))
      (node (ref "T1") (pin "15") (pinfunction "15_15") (pintype "passive"))
    )
    (net (code "61") (name "Net-(R7-Pad2)") (class "Default")
      (node (ref "R7") (pin "2") (pinfunction "2_2") (pintype "passive"))
      (node (ref "R8") (pin "1") (pinfunction "1_1") (pintype "passive"))
      (node (ref "R9") (pin "2") (pinfunction "2_2") (pintype "passive"))
    )
    (net (code "62") (name "Net-(R10-Pad2)") (class "Default")
      (node (ref "R10") (pin "2") (pinfunction "2_2") (pintype "passive"))
      (node (ref "T1") (pin "10") (pinfunction "10_10") (pintype "passive"))
    )
    (net (code "63") (name "Net-(R11-Pad2)") (class "Default")
      (node (ref "R11") (pin "2") (pinfunction "2_2") (pintype "passive"))
      (node (ref "R13") (pin "1") (pinfunction "1_1") (pintype "passive"))
      (node (ref "R14") (pin "2") (pinfunction "2_2") (pintype "passive"))
    )
    (net (code "64") (name "Net-(R20-Pad2)") (class "Default")
      (node (ref "R20") (pin "2") (pinfunction "2_2") (pintype "passive"))
      (node (ref "R23") (pin "2") (pinfunction "2_2") (pintype "passive"))
      (node (ref "T2") (pin "1") (pinfunction "1_1") (pintype "passive"))
    )
    (net (code "65") (name "Net-(R21-Pad2)") (class "Default")
      (node (ref "R21") (pin "2") (pinfunction "2_2") (pintype "passive"))
      (node (ref "R25") (pin "2") (pinfunction "2_2") (pintype "passive"))
      (node (ref "T2") (pin "3") (pinfunction "3_3") (pintype "passive"))
    )
    (net (code "66") (name "Net-(R24-Pad2)") (class "Default")
      (node (ref "R24") (pin "2") (pinfunction "2_2") (pintype "passive"))
      (node (ref "T2") (pin "15") (pinfunction "15_15") (pintype "passive"))
    )
    (net (code "67") (name "Net-(R26-Pad2)") (class "Default")
      (node (ref "R26") (pin "2") (pinfunction "2_2") (pintype "passive"))
      (node (ref "R27") (pin "1") (pinfunction "1_1") (pintype "passive"))
      (node (ref "R28") (pin "2") (pinfunction "2_2") (pintype "passive"))
    )
    (net (code "68") (name "Net-(R29-Pad2)") (class "Default")
      (node (ref "R29") (pin "2") (pinfunction "2_2") (pintype "passive"))
      (node (ref "T2") (pin "10") (pinfunction "10_10") (pintype "passive"))
    )
    (net (code "69") (name "Net-(R30-Pad2)") (class "Default")
      (node (ref "R30") (pin "2") (pinfunction "2_2") (pintype "passive"))
      (node (ref "R32") (pin "1") (pinfunction "1_1") (pintype "passive"))
      (node (ref "R33") (pin "2") (pinfunction "2_2") (pintype "passive"))
    )
    (net (code "70") (name "unconnected-(J2-Pad4)") (class "Default")
      (node (ref "J2") (pin "4") (pinfunction "4_4") (pintype "passive+no_connect"))
    )
    (net (code "71") (name "unconnected-(J2-Pad5)") (class "Default")
      (node (ref "J2") (pin "5") (pinfunction "5_5") (pintype "passive+no_connect"))
    )
    (net (code "72") (name "unconnected-(J3-Pad4)") (class "Default")
      (node (ref "J3") (pin "4") (pinfunction "4_4") (pintype "passive+no_connect"))
    )
    (net (code "73") (name "unconnected-(J3-Pad5)") (class "Default")
      (node (ref "J3") (pin "5") (pinfunction "5_5") (pintype "passive+no_connect"))
    )
  )
)
